# RIAA.net
KiCad netlist of a schematic drawn in Altium Designer
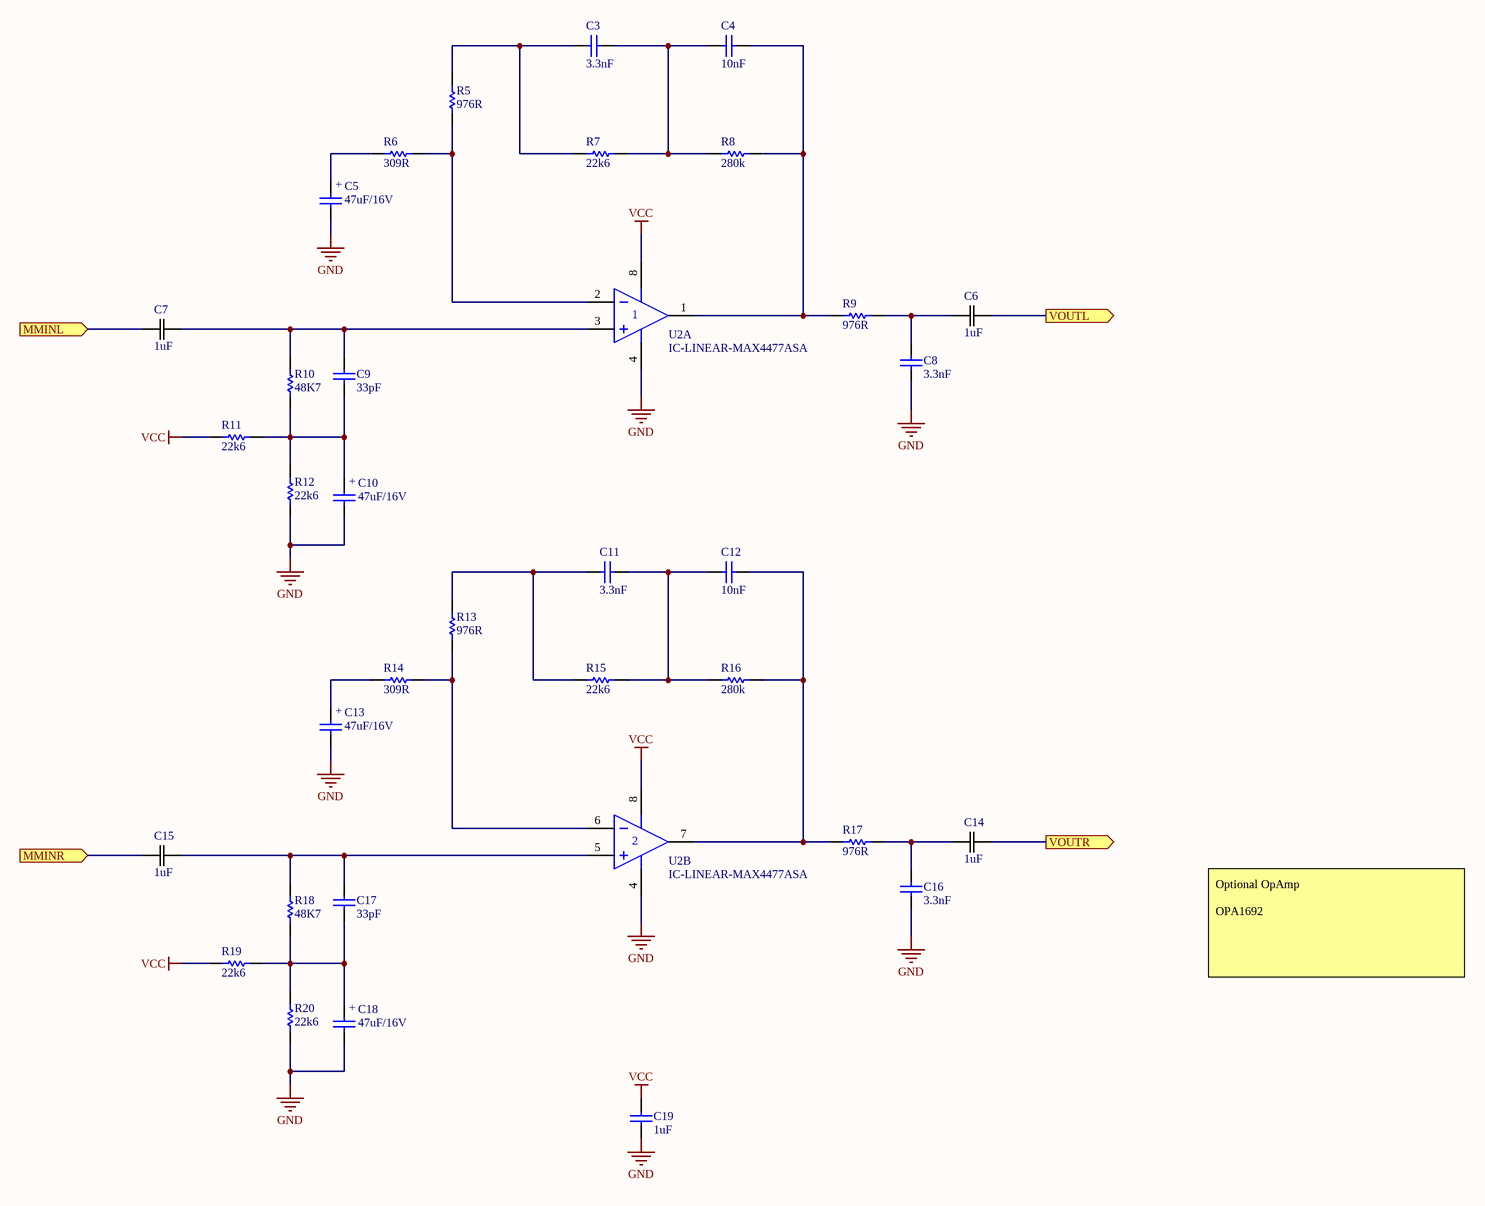
[diagram p0: RIAA.SchDoc]

(export (version "E")
  (design (tool "Eeschema 10.0.6"))
  (components
    (comp (ref "C3")
      (value "3.3nF")
      (footprint "CAPC0805(2012)100_N")
      (description "CAP 3.3nF 16V ±1% 0805 (2012 Metric) Thickness 1mm SMD")
      (fields (field (name "TOLERANCE") "Â±1%") (field (name "Comment") "CAP 3.3nF 16V 0805(2012)"))
      (libsource (lib "Altium Content Vault") (part "CMP-1036-03397-1"))
    )
    (comp (ref "C4")
      (value "10nF")
      (footprint "CAPC0805(2012)145_N")
      (description "CAP 10nF 16V ±5% 0805 (2012 Metric) Thickness 1.45mm SMD")
      (fields (field (name "TOLERANCE") "Â±5%") (field (name "Comment") "CAP 10nF 16V 0805(2012)"))
      (libsource (lib "Altium Content Vault") (part "CMP-1036-03817-1"))
    )
    (comp (ref "C5")
      (value "47uF/16V")
      (footprint "CAPP_5x5.4")
      (description "47µF 16V Aluminum Electrolytic Capacitors Radial, Can - SMD 1000 Hrs @ 85°C")
      (fields (field (name "MPN") "EEE-1CA470WR"))
      (libsource (lib "micun") (part "CAPP_47UF16V_EEE-1CA470WR"))
    )
    (comp (ref "C6")
      (value "1uF")
      (footprint "CAP_ECPU_G2")
      (description "1µF Film Capacitor  16V Acrylic, Metallized - Stacked 1210 (3225 Metric)")
      (fields (field (name "MPN") "ECP-U1C105MA5"))
      (libsource (lib "micun") (part "CAP-ECP-U1C105MA5"))
    )
    (comp (ref "C7")
      (value "1uF")
      (footprint "CAP_ECPU_G2")
      (description "1µF Film Capacitor  16V Acrylic, Metallized - Stacked 1210 (3225 Metric)")
      (fields (field (name "MPN") "ECP-U1C105MA5"))
      (libsource (lib "micun") (part "CAP-ECP-U1C105MA5"))
    )
    (comp (ref "C8")
      (value "3.3nF")
      (footprint "CAPC0805(2012)100_N")
      (description "CAP 3.3nF 16V ±1% 0805 (2012 Metric) Thickness 1mm SMD")
      (fields (field (name "TOLERANCE") "Â±1%") (field (name "Comment") "CAP 3.3nF 16V 0805(2012)"))
      (libsource (lib "Altium Content Vault") (part "CMP-1036-03397-1"))
    )
    (comp (ref "C9")
      (value "33pF")
      (footprint "CAPC0805(2012)100_N")
      (description "CAP 33pF 16V ±1% 0805 (2012 Metric) Thickness 1mm SMD")
      (fields (field (name "TOLERANCE") "Â±1%") (field (name "Comment") "CAP 33pF 16V 0805(2012)"))
      (libsource (lib "Altium Content Vault") (part "CMP-1036-01404-1"))
    )
    (comp (ref "C10")
      (value "47uF/16V")
      (footprint "CAPP_5x5.4")
      (description "47µF 16V Aluminum Electrolytic Capacitors Radial, Can - SMD 1000 Hrs @ 85°C")
      (fields (field (name "MPN") "EEE-1CA470WR"))
      (libsource (lib "micun") (part "CAPP_47UF16V_EEE-1CA470WR"))
    )
    (comp (ref "C11")
      (value "3.3nF")
      (footprint "CAPC0805(2012)100_N")
      (description "CAP 3.3nF 16V ±1% 0805 (2012 Metric) Thickness 1mm SMD")
      (fields (field (name "TOLERANCE") "Â±1%") (field (name "Comment") "CAP 3.3nF 16V 0805(2012)"))
      (libsource (lib "Altium Content Vault") (part "CMP-1036-03397-1"))
    )
    (comp (ref "C12")
      (value "10nF")
      (footprint "CAPC0805(2012)145_N")
      (description "CAP 10nF 16V ±5% 0805 (2012 Metric) Thickness 1.45mm SMD")
      (fields (field (name "TOLERANCE") "Â±5%") (field (name "Comment") "CAP 10nF 16V 0805(2012)"))
      (libsource (lib "Altium Content Vault") (part "CMP-1036-03817-1"))
    )
    (comp (ref "C13")
      (value "47uF/16V")
      (footprint "CAPP_5x5.4")
      (description "47µF 16V Aluminum Electrolytic Capacitors Radial, Can - SMD 1000 Hrs @ 85°C")
      (fields (field (name "MPN") "EEE-1CA470WR"))
      (libsource (lib "micun") (part "CAPP_47UF16V_EEE-1CA470WR"))
    )
    (comp (ref "C14")
      (value "1uF")
      (footprint "CAP_ECPU_G2")
      (description "1µF Film Capacitor  16V Acrylic, Metallized - Stacked 1210 (3225 Metric)")
      (fields (field (name "MPN") "ECP-U1C105MA5"))
      (libsource (lib "micun") (part "CAP-ECP-U1C105MA5"))
    )
    (comp (ref "C15")
      (value "1uF")
      (footprint "CAP_ECPU_G2")
      (description "1µF Film Capacitor  16V Acrylic, Metallized - Stacked 1210 (3225 Metric)")
      (fields (field (name "MPN") "ECP-U1C105MA5"))
      (libsource (lib "micun") (part "CAP-ECP-U1C105MA5"))
    )
    (comp (ref "C16")
      (value "3.3nF")
      (footprint "CAPC0805(2012)100_N")
      (description "CAP 3.3nF 16V ±1% 0805 (2012 Metric) Thickness 1mm SMD")
      (fields (field (name "TOLERANCE") "Â±1%") (field (name "Comment") "CAP 3.3nF 16V 0805(2012)"))
      (libsource (lib "Altium Content Vault") (part "CMP-1036-03397-1"))
    )
    (comp (ref "C17")
      (value "33pF")
      (footprint "CAPC0805(2012)100_N")
      (description "CAP 33pF 16V ±1% 0805 (2012 Metric) Thickness 1mm SMD")
      (fields (field (name "TOLERANCE") "Â±1%") (field (name "Comment") "CAP 33pF 16V 0805(2012)"))
      (libsource (lib "Altium Content Vault") (part "CMP-1036-01404-1"))
    )
    (comp (ref "C18")
      (value "47uF/16V")
      (footprint "CAPP_5x5.4")
      (description "47µF 16V Aluminum Electrolytic Capacitors Radial, Can - SMD 1000 Hrs @ 85°C")
      (fields (field (name "MPN") "EEE-1CA470WR"))
      (libsource (lib "micun") (part "CAPP_47UF16V_EEE-1CA470WR"))
    )
    (comp (ref "C19")
      (value "1uF")
      (footprint "CAPC0805(2012)145_N")
      (description "CAP 1uF 16V ±20% 0805 (2012 Metric) Thickness 1.45mm SMD")
      (fields (field (name "TOLERANCE") "Â±20%") (field (name "Comment") "CAP 1uF 16V 0805(2012)"))
      (libsource (lib "Altium Content Vault") (part "CMP-1036-04748-1"))
    )
    (comp (ref "R5")
      (value "976R")
      (footprint "RESC0805(2012)_N")
      (description "976R 0.125W 1% 0805 (2012 Metric)  SMD")
      (fields (field (name "POWER") "0.125 W") (field (name "TOLERANCE") "1 %"))
      (libsource (lib "Altium Content Vault") (part "RES"))
    )
    (comp (ref "R6")
      (value "309R")
      (footprint "RESC0805(2012)_N")
      (description "309R 0.125W 1% 0805 (2012 Metric)  SMD")
      (fields (field (name "TOLERANCE") "1 %") (field (name "POWER") "0.125 W"))
      (libsource (lib "Altium Content Vault") (part "CMP-1013-00451-1"))
    )
    (comp (ref "R7")
      (value "22k6")
      (footprint "RESC0805(2012)_N")
      (description "22K6 0.125W 1% 0805 (2012 Metric)  SMD")
      (fields (field (name "TOLERANCE") "1 %") (field (name "POWER") "0.125 W"))
      (libsource (lib "Altium Content Vault") (part "CMP-1013-00661-1"))
    )
    (comp (ref "R8")
      (value "280k")
      (footprint "RESC0805(2012)_N")
      (description "280K 0.125W 1% 0805 (2012 Metric)  SMD")
      (fields (field (name "TOLERANCE") "1 %") (field (name "POWER") "0.125 W"))
      (libsource (lib "Altium Content Vault") (part "CMP-1013-00785-1"))
    )
    (comp (ref "R9")
      (value "976R")
      (footprint "RESC0805(2012)_N")
      (description "976R 0.125W 1% 0805 (2012 Metric)  SMD")
      (fields (field (name "POWER") "0.125 W") (field (name "TOLERANCE") "1 %"))
      (libsource (lib "Altium Content Vault") (part "RES"))
    )
    (comp (ref "R10")
      (value "48K7")
      (footprint "RESC0805(2012)_N")
      (description "48K7 0.125W 1% 0805 (2012 Metric)  SMD")
      (fields (field (name "TOLERANCE") "1 %") (field (name "POWER") "0.125 W"))
      (libsource (lib "Altium Content Vault") (part "RES"))
    )
    (comp (ref "R11")
      (value "22k6")
      (footprint "RESC0805(2012)_N")
      (description "22K6 0.125W 1% 0805 (2012 Metric)  SMD")
      (fields (field (name "TOLERANCE") "1 %") (field (name "POWER") "0.125 W"))
      (libsource (lib "Altium Content Vault") (part "CMP-1013-00661-1"))
    )
    (comp (ref "R12")
      (value "22k6")
      (footprint "RESC0805(2012)_N")
      (description "22K6 0.125W 1% 0805 (2012 Metric)  SMD")
      (fields (field (name "TOLERANCE") "1 %") (field (name "POWER") "0.125 W"))
      (libsource (lib "Altium Content Vault") (part "CMP-1013-00661-1"))
    )
    (comp (ref "R13")
      (value "976R")
      (footprint "RESC0805(2012)_N")
      (description "976R 0.125W 1% 0805 (2012 Metric)  SMD")
      (fields (field (name "POWER") "0.125 W") (field (name "TOLERANCE") "1 %"))
      (libsource (lib "Altium Content Vault") (part "RES"))
    )
    (comp (ref "R14")
      (value "309R")
      (footprint "RESC0805(2012)_N")
      (description "309R 0.125W 1% 0805 (2012 Metric)  SMD")
      (fields (field (name "TOLERANCE") "1 %") (field (name "POWER") "0.125 W"))
      (libsource (lib "Altium Content Vault") (part "CMP-1013-00451-1"))
    )
    (comp (ref "R15")
      (value "22k6")
      (footprint "RESC0805(2012)_N")
      (description "22K6 0.125W 1% 0805 (2012 Metric)  SMD")
      (fields (field (name "TOLERANCE") "1 %") (field (name "POWER") "0.125 W"))
      (libsource (lib "Altium Content Vault") (part "CMP-1013-00661-1"))
    )
    (comp (ref "R16")
      (value "280k")
      (footprint "RESC0805(2012)_N")
      (description "280K 0.125W 1% 0805 (2012 Metric)  SMD")
      (fields (field (name "TOLERANCE") "1 %") (field (name "POWER") "0.125 W"))
      (libsource (lib "Altium Content Vault") (part "CMP-1013-00785-1"))
    )
    (comp (ref "R17")
      (value "976R")
      (footprint "RESC0805(2012)_N")
      (description "976R 0.125W 1% 0805 (2012 Metric)  SMD")
      (fields (field (name "POWER") "0.125 W") (field (name "TOLERANCE") "1 %"))
      (libsource (lib "Altium Content Vault") (part "RES"))
    )
    (comp (ref "R18")
      (value "48K7")
      (footprint "RESC0805(2012)_N")
      (description "48K7 0.125W 1% 0805 (2012 Metric)  SMD")
      (fields (field (name "TOLERANCE") "1 %") (field (name "POWER") "0.125 W"))
      (libsource (lib "Altium Content Vault") (part "RES"))
    )
    (comp (ref "R19")
      (value "22k6")
      (footprint "RESC0805(2012)_N")
      (description "22K6 0.125W 1% 0805 (2012 Metric)  SMD")
      (fields (field (name "TOLERANCE") "1 %") (field (name "POWER") "0.125 W"))
      (libsource (lib "Altium Content Vault") (part "CMP-1013-00661-1"))
    )
    (comp (ref "R20")
      (value "22k6")
      (footprint "RESC0805(2012)_N")
      (description "22K6 0.125W 1% 0805 (2012 Metric)  SMD")
      (fields (field (name "TOLERANCE") "1 %") (field (name "POWER") "0.125 W"))
      (libsource (lib "Altium Content Vault") (part "CMP-1013-00661-1"))
    )
    (comp (ref "U2")
      (value "IC-LINEAR-MAX4477ASA")
      (footprint "SOIC8_N")
      (description "Dual Rail-to-Rail output  Low-Power Operational Amplifier")
      (fields (field (name "MPN") "MAX4477ASA+"))
      (libsource (lib "micun") (part "IC-LINEAR-MAX4477ASA"))
    )
  )
  (nets
    (net (code "1") (name "/MMINL") (class "Default")
      (node (ref "C7") (pin "1") (pinfunction "1_1") (pintype "passive"))
    )
    (net (code "2") (name "/MMINR") (class "Default")
      (node (ref "C15") (pin "1") (pinfunction "1_1") (pintype "passive"))
    )
    (net (code "3") (name "/VOUTL") (class "Default")
      (node (ref "C6") (pin "2") (pinfunction "2_2") (pintype "passive"))
    )
    (net (code "4") (name "/VOUTR") (class "Default")
      (node (ref "C14") (pin "2") (pinfunction "2_2") (pintype "passive"))
    )
    (net (code "5") (name "GND") (class "Default")
      (node (ref "C10") (pin "2") (pinfunction "2_2") (pintype "passive"))
      (node (ref "C13") (pin "2") (pinfunction "2_2") (pintype "passive"))
      (node (ref "C16") (pin "1") (pinfunction "1_1") (pintype "passive"))
      (node (ref "C18") (pin "2") (pinfunction "2_2") (pintype "passive"))
      (node (ref "C19") (pin "1") (pinfunction "1_1") (pintype "passive"))
      (node (ref "C5") (pin "2") (pinfunction "2_2") (pintype "passive"))
      (node (ref "C8") (pin "1") (pinfunction "1_1") (pintype "passive"))
      (node (ref "R12") (pin "1") (pinfunction "1_1") (pintype "passive"))
      (node (ref "R20") (pin "1") (pinfunction "1_1") (pintype "passive"))
      (node (ref "U2") (pin "4") (pinfunction "V-_4") (pintype "power_in"))
    )
    (net (code "6") (name "Net-(C3-Pad1)") (class "Default")
      (node (ref "C3") (pin "1") (pinfunction "1_1") (pintype "passive"))
      (node (ref "C4") (pin "1") (pinfunction "1_1") (pintype "passive"))
      (node (ref "R7") (pin "2") (pinfunction "2_2") (pintype "passive"))
      (node (ref "R8") (pin "1") (pinfunction "1_1") (pintype "passive"))
    )
    (net (code "7") (name "Net-(C3-Pad2)") (class "Default")
      (node (ref "C3") (pin "2") (pinfunction "2_2") (pintype "passive"))
      (node (ref "R5") (pin "2") (pinfunction "2_2") (pintype "passive"))
      (node (ref "R7") (pin "1") (pinfunction "1_1") (pintype "passive"))
    )
    (net (code "8") (name "Net-(C5-Pad1)") (class "Default")
      (node (ref "C5") (pin "1") (pinfunction "1_1") (pintype "passive"))
      (node (ref "R6") (pin "1") (pinfunction "1_1") (pintype "passive"))
    )
    (net (code "9") (name "Net-(C6-Pad1)") (class "Default")
      (node (ref "C6") (pin "1") (pinfunction "1_1") (pintype "passive"))
      (node (ref "C8") (pin "2") (pinfunction "2_2") (pintype "passive"))
      (node (ref "R9") (pin "1") (pinfunction "1_1") (pintype "passive"))
    )
    (net (code "10") (name "Net-(C10-Pad1)") (class "Default")
      (node (ref "C10") (pin "1") (pinfunction "1_1") (pintype "passive"))
      (node (ref "C9") (pin "1") (pinfunction "1_1") (pintype "passive"))
      (node (ref "R10") (pin "2") (pinfunction "2_2") (pintype "passive"))
      (node (ref "R11") (pin "2") (pinfunction "2_2") (pintype "passive"))
      (node (ref "R12") (pin "2") (pinfunction "2_2") (pintype "passive"))
    )
    (net (code "11") (name "Net-(C11-Pad1)") (class "Default")
      (node (ref "C11") (pin "1") (pinfunction "1_1") (pintype "passive"))
      (node (ref "C12") (pin "1") (pinfunction "1_1") (pintype "passive"))
      (node (ref "R15") (pin "2") (pinfunction "2_2") (pintype "passive"))
      (node (ref "R16") (pin "1") (pinfunction "1_1") (pintype "passive"))
    )
    (net (code "12") (name "Net-(C11-Pad2)") (class "Default")
      (node (ref "C11") (pin "2") (pinfunction "2_2") (pintype "passive"))
      (node (ref "R13") (pin "2") (pinfunction "2_2") (pintype "passive"))
      (node (ref "R15") (pin "1") (pinfunction "1_1") (pintype "passive"))
    )
    (net (code "13") (name "Net-(C13-Pad1)") (class "Default")
      (node (ref "C13") (pin "1") (pinfunction "1_1") (pintype "passive"))
      (node (ref "R14") (pin "1") (pinfunction "1_1") (pintype "passive"))
    )
    (net (code "14") (name "Net-(C14-Pad1)") (class "Default")
      (node (ref "C14") (pin "1") (pinfunction "1_1") (pintype "passive"))
      (node (ref "C16") (pin "2") (pinfunction "2_2") (pintype "passive"))
      (node (ref "R17") (pin "1") (pinfunction "1_1") (pintype "passive"))
    )
    (net (code "15") (name "Net-(C17-Pad1)") (class "Default")
      (node (ref "C17") (pin "1") (pinfunction "1_1") (pintype "passive"))
      (node (ref "C18") (pin "1") (pinfunction "1_1") (pintype "passive"))
      (node (ref "R18") (pin "2") (pinfunction "2_2") (pintype "passive"))
      (node (ref "R19") (pin "2") (pinfunction "2_2") (pintype "passive"))
      (node (ref "R20") (pin "2") (pinfunction "2_2") (pintype "passive"))
    )
    (net (code "16") (name "Net-(U2A-IN1+)") (class "Default")
      (node (ref "C7") (pin "2") (pinfunction "2_2") (pintype "passive"))
      (node (ref "C9") (pin "2") (pinfunction "2_2") (pintype "passive"))
      (node (ref "R10") (pin "1") (pinfunction "1_1") (pintype "passive"))
      (node (ref "U2") (pin "3") (pinfunction "IN1+_3") (pintype "passive"))
    )
    (net (code "17") (name "Net-(U2A-IN1-)") (class "Default")
      (node (ref "R5") (pin "1") (pinfunction "1_1") (pintype "passive"))
      (node (ref "R6") (pin "2") (pinfunction "2_2") (pintype "passive"))
      (node (ref "U2") (pin "2") (pinfunction "IN1-_2") (pintype "passive"))
    )
    (net (code "18") (name "Net-(U2A-OUT1)") (class "Default")
      (node (ref "C4") (pin "2") (pinfunction "2_2") (pintype "passive"))
      (node (ref "R8") (pin "2") (pinfunction "2_2") (pintype "passive"))
      (node (ref "R9") (pin "2") (pinfunction "2_2") (pintype "passive"))
      (node (ref "U2") (pin "1") (pinfunction "OUT1_1") (pintype "passive"))
    )
    (net (code "19") (name "Net-(U2B-IN2+)") (class "Default")
      (node (ref "C15") (pin "2") (pinfunction "2_2") (pintype "passive"))
      (node (ref "C17") (pin "2") (pinfunction "2_2") (pintype "passive"))
      (node (ref "R18") (pin "1") (pinfunction "1_1") (pintype "passive"))
      (node (ref "U2") (pin "5") (pinfunction "IN2+_5") (pintype "passive"))
    )
    (net (code "20") (name "Net-(U2B-IN2-)") (class "Default")
      (node (ref "R13") (pin "1") (pinfunction "1_1") (pintype "passive"))
      (node (ref "R14") (pin "2") (pinfunction "2_2") (pintype "passive"))
      (node (ref "U2") (pin "6") (pinfunction "IN2-_6") (pintype "passive"))
    )
    (net (code "21") (name "Net-(U2B-OUT2)") (class "Default")
      (node (ref "C12") (pin "2") (pinfunction "2_2") (pintype "passive"))
      (node (ref "R16") (pin "2") (pinfunction "2_2") (pintype "passive"))
      (node (ref "R17") (pin "2") (pinfunction "2_2") (pintype "passive"))
      (node (ref "U2") (pin "7") (pinfunction "OUT2_7") (pintype "passive"))
    )
    (net (code "22") (name "VCC") (class "Default")
      (node (ref "C19") (pin "2") (pinfunction "2_2") (pintype "passive"))
      (node (ref "R11") (pin "1") (pinfunction "1_1") (pintype "passive"))
      (node (ref "R19") (pin "1") (pinfunction "1_1") (pintype "passive"))
      (node (ref "U2") (pin "8") (pinfunction "V+_8") (pintype "power_in"))
    )
  )
)
